# LNA-fantom.net
KiCad netlist of a schematic drawn in EAGLE
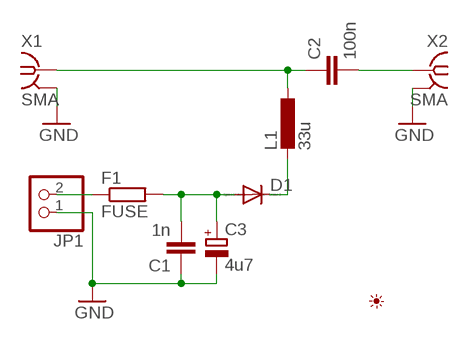
[diagram p0: schematic, sheet 1]

(export (version "E")
  (design (tool "Eeschema 10.0.6"))
  (components
    (comp (ref "C1")
      (value "1n")
      (footprint "eagle-import:C0805")
      (libsource (lib "eagle-import") (part "C-EUC0805"))
    )
    (comp (ref "C2")
      (value "100n")
      (footprint "eagle-import:C0805")
      (libsource (lib "eagle-import") (part "C-EUC0805"))
    )
    (comp (ref "C3")
      (value "4u7")
      (footprint "eagle-import:SMC_A")
      (libsource (lib "eagle-import") (part "CPOL-EUSMCA"))
    )
    (comp (ref "D1")
      (value "DIODE-MINIMELF")
      (footprint "eagle-import:MINIMELF")
      (libsource (lib "eagle-import") (part "DIODE-MINIMELF"))
    )
    (comp (ref "F1")
      (value "FUSE")
      (footprint "eagle-import:R1210")
      (libsource (lib "eagle-import") (part "R-EU_R1210"))
    )
    (comp (ref "JP1")
      (value "PINHD-1X2")
      (footprint "eagle-import:1X02")
      (libsource (lib "eagle-import") (part "PINHD-1X2"))
    )
    (comp (ref "L1")
      (value "33u")
      (footprint "eagle-import:POWER-CHOKE_WE-TPC")
      (libsource (lib "eagle-import") (part "L-EUWE-TPC"))
    )
    (comp (ref "U$1")
      (value "PICTO_1")
      (footprint "eagle-import:PICTO_1")
      (libsource (lib "eagle-import") (part "PICTO_1"))
    )
    (comp (ref "X1")
      (value "SMA")
      (footprint "eagle-import:J502-ND-142-0701-801_806")
      (fields (field (name "MF") "JOHNSON COMPONENTS") (field (name "MPN") "142-0701-801"))
      (libsource (lib "eagle-import") (part "SMA-142-0701-801/806"))
    )
    (comp (ref "X2")
      (value "SMA")
      (footprint "eagle-import:J502-ND-142-0701-801_806")
      (fields (field (name "MF") "JOHNSON COMPONENTS") (field (name "MPN") "142-0701-801"))
      (libsource (lib "eagle-import") (part "SMA-142-0701-801/806"))
    )
  )
  (nets
    (net (code "1") (name "GND") (class "Default")
      (node (ref "C1") (pin "1") (pinfunction "1_1") (pintype "passive"))
      (node (ref "C3") (pin "-") (pinfunction "-_-") (pintype "passive"))
      (node (ref "JP1") (pin "1") (pinfunction "1_1") (pintype "passive"))
      (node (ref "X1") (pin "G@1") (pinfunction "2_G@1") (pintype "passive"))
      (node (ref "X1") (pin "G@2") (pinfunction "2_G@2") (pintype "passive"))
      (node (ref "X1") (pin "G@3") (pinfunction "2_G@3") (pintype "passive"))
      (node (ref "X1") (pin "G@4") (pinfunction "2_G@4") (pintype "passive"))
      (node (ref "X2") (pin "G@1") (pinfunction "2_G@1") (pintype "passive"))
      (node (ref "X2") (pin "G@2") (pinfunction "2_G@2") (pintype "passive"))
      (node (ref "X2") (pin "G@3") (pinfunction "2_G@3") (pintype "passive"))
      (node (ref "X2") (pin "G@4") (pinfunction "2_G@4") (pintype "passive"))
    )
    (net (code "2") (name "Net-(C1-Pad2)") (class "Default")
      (node (ref "C1") (pin "2") (pinfunction "2_2") (pintype "passive"))
      (node (ref "C3") (pin "+") (pinfunction "+_+") (pintype "passive"))
      (node (ref "D1") (pin "A") (pinfunction "A_A") (pintype "passive"))
      (node (ref "F1") (pin "2") (pinfunction "2_2") (pintype "passive"))
    )
    (net (code "3") (name "Net-(C2-Pad1)") (class "Default")
      (node (ref "C2") (pin "1") (pinfunction "1_1") (pintype "passive"))
      (node (ref "L1") (pin "1") (pinfunction "1_1") (pintype "passive"))
      (node (ref "X1") (pin "1") (pinfunction "1_1") (pintype "passive"))
    )
    (net (code "4") (name "Net-(C2-Pad2)") (class "Default")
      (node (ref "C2") (pin "2") (pinfunction "2_2") (pintype "passive"))
      (node (ref "X2") (pin "1") (pinfunction "1_1") (pintype "passive"))
    )
    (net (code "5") (name "Net-(D1-PadC)") (class "Default")
      (node (ref "D1") (pin "C") (pinfunction "C_C") (pintype "passive"))
      (node (ref "L1") (pin "2") (pinfunction "2_2") (pintype "passive"))
    )
    (net (code "6") (name "Net-(F1-Pad1)") (class "Default")
      (node (ref "F1") (pin "1") (pinfunction "1_1") (pintype "passive"))
      (node (ref "JP1") (pin "2") (pinfunction "2_2") (pintype "passive"))
    )
  )
)
